# Pi_Tracker2.net
KiCad netlist of a schematic drawn in EAGLE
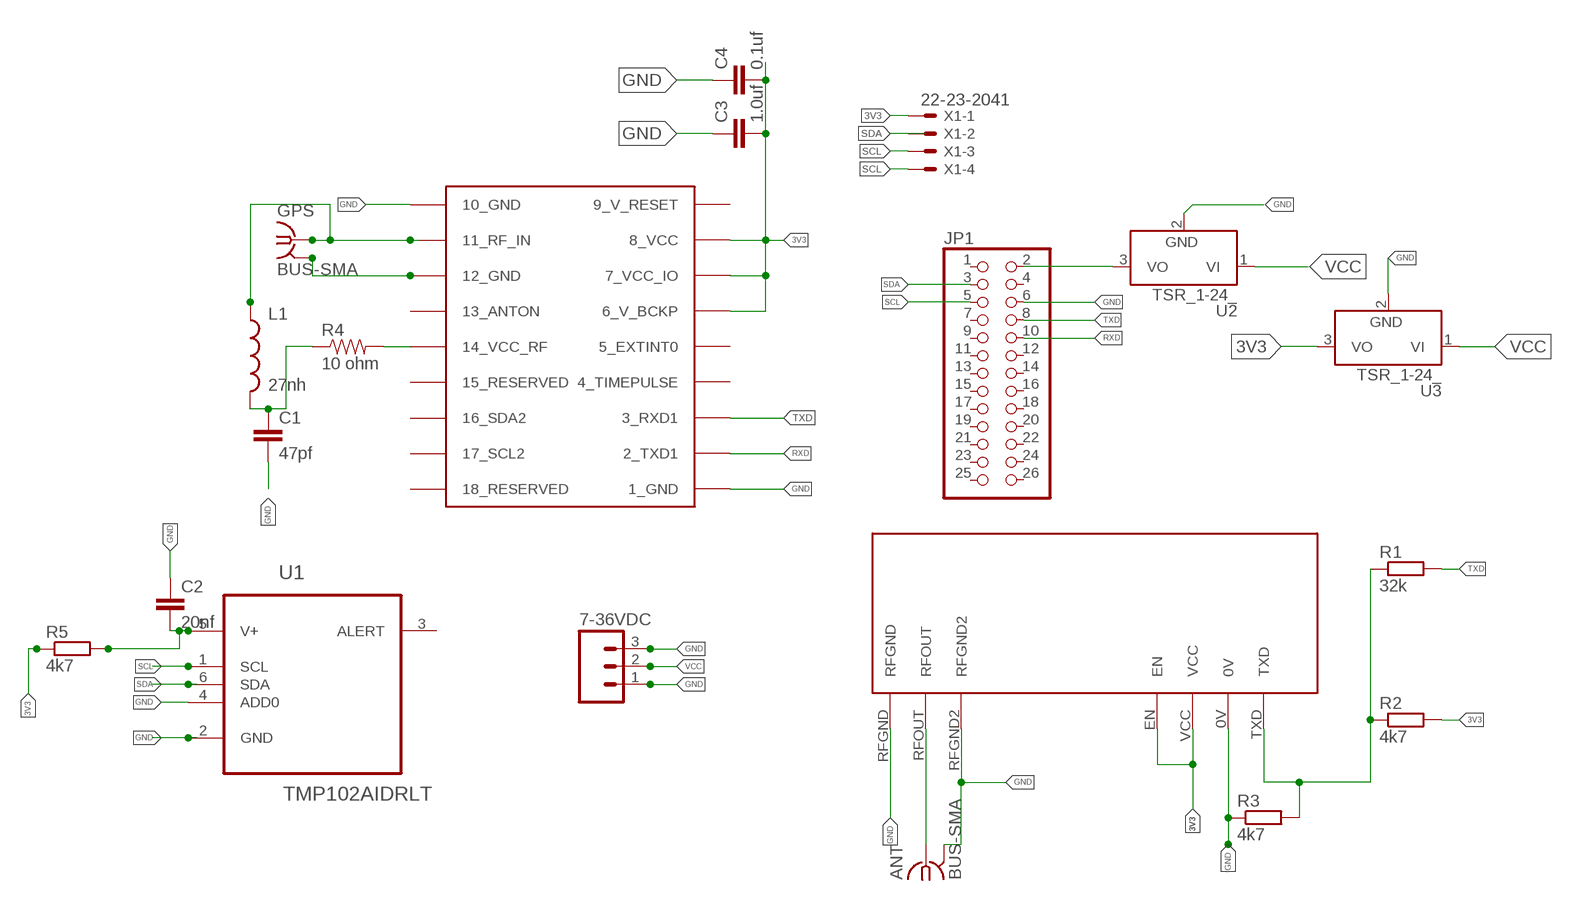
[diagram p0: schematic, sheet 1]

(export (version "E")
  (design (tool "Eeschema 10.0.6"))
  (components
    (comp (ref "7-36VDC")
      (value "M03PTH")
      (footprint "eagle-import:1X03")
      (libsource (lib "eagle-import") (part "M03PTH"))
    )
    (comp (ref "ANT")
      (value "BUS-SMA")
      (footprint "eagle-import:BUS-SMA")
      (libsource (lib "eagle-import") (part "BUS-SMA"))
    )
    (comp (ref "C1")
      (value "47pf")
      (footprint "eagle-import:0603-CAP")
      (libsource (lib "eagle-import") (part "CAP0603-CAP"))
    )
    (comp (ref "C2")
      (value "20nf")
      (footprint "eagle-import:C0603")
      (libsource (lib "eagle-import") (part "C-EUC0603"))
    )
    (comp (ref "C3")
      (value "1.0uf")
      (footprint "eagle-import:C0603")
      (libsource (lib "eagle-import") (part "C-EUC0603"))
    )
    (comp (ref "C4")
      (value "0.1uf")
      (footprint "eagle-import:C0603")
      (libsource (lib "eagle-import") (part "C-EUC0603"))
    )
    (comp (ref "GPS")
      (value "BUS-SMA")
      (footprint "eagle-import:BUS-SMA")
      (libsource (lib "eagle-import") (part "BUS-SMA"))
    )
    (comp (ref "JP1")
      (value "PINHD-2X13")
      (footprint "eagle-import:2X13")
      (libsource (lib "eagle-import") (part "PINHD-2X13"))
    )
    (comp (ref "L1")
      (value "27nh")
      (footprint "eagle-import:0603")
      (libsource (lib "eagle-import") (part "INDUCTOR0603"))
    )
    (comp (ref "R1")
      (value "32k")
      (footprint "eagle-import:R0603")
      (libsource (lib "eagle-import") (part "R-EU_R0603"))
    )
    (comp (ref "R2")
      (value "4k7")
      (footprint "eagle-import:R0603")
      (libsource (lib "eagle-import") (part "R-EU_R0603"))
    )
    (comp (ref "R3")
      (value "4k7")
      (footprint "eagle-import:R0603")
      (libsource (lib "eagle-import") (part "R-EU_R0603"))
    )
    (comp (ref "R4")
      (value "10 ohm")
      (footprint "eagle-import:0603-RES")
      (libsource (lib "eagle-import") (part "RESISTOR0603"))
    )
    (comp (ref "R5")
      (value "4k7")
      (footprint "eagle-import:R0603")
      (libsource (lib "eagle-import") (part "R-EU_R0603"))
    )
    (comp (ref "U$1")
      (value "NTX2")
      (footprint "eagle-import:NTX2")
      (libsource (lib "eagle-import") (part "NTX2"))
    )
    (comp (ref "U$2")
      (value "UBLOX_MAX")
      (footprint "eagle-import:UBLOX_MAX")
      (libsource (lib "eagle-import") (part "UBLOX_MAX"))
    )
    (comp (ref "U1")
      (value "TMP102AIDRLT")
      (footprint "eagle-import:SOT50P160X60-6N")
      (libsource (lib "eagle-import") (part "TMP102AIDRLT"))
    )
    (comp (ref "U2")
      (value "TSR_1-24_")
      (footprint "eagle-import:TSR-1")
      (libsource (lib "eagle-import") (part "TSR_1-24_"))
    )
    (comp (ref "U3")
      (value "TSR_1-24_")
      (footprint "eagle-import:TSR-1")
      (libsource (lib "eagle-import") (part "TSR_1-24_"))
    )
    (comp (ref "X1")
      (value "22-23-2041")
      (footprint "eagle-import:22-23-2041")
      (fields (field (name "MF") "MOLEX"))
      (libsource (lib "eagle-import") (part "22-23-2041"))
    )
  )
  (nets
    (net (code "1") (name "/9_V_RESET") (class "Default")
      (node (ref "U$2") (pin "9_V_RESET") (pinfunction "9_V_RESET_9_V_RESET") (pintype "power_in"))
    )
    (net (code "2") (name "3V3") (class "Default")
      (node (ref "C2") (pin "2") (pinfunction "2_2") (pintype "passive"))
      (node (ref "C3") (pin "2") (pinfunction "2_2") (pintype "passive"))
      (node (ref "C4") (pin "2") (pinfunction "2_2") (pintype "passive"))
      (node (ref "R2") (pin "2") (pinfunction "2_2") (pintype "passive"))
      (node (ref "R5") (pin "1") (pinfunction "1_1") (pintype "passive"))
      (node (ref "R5") (pin "2") (pinfunction "2_2") (pintype "passive"))
      (node (ref "U$1") (pin "EN") (pinfunction "EN_EN") (pintype "bidirectional"))
      (node (ref "U$1") (pin "VCC") (pinfunction "VCC_VCC") (pintype "bidirectional"))
      (node (ref "U$2") (pin "6_V_BCKP") (pinfunction "6_V_BCKP_6_V_BCKP") (pintype "bidirectional"))
      (node (ref "U$2") (pin "7_VCC_IO") (pinfunction "7_VCC_IO_7_VCC_IO") (pintype "power_in"))
      (node (ref "U$2") (pin "8_VCC") (pinfunction "8_VCC_8_VCC") (pintype "power_in"))
      (node (ref "U1") (pin "5") (pinfunction "V+_5") (pintype "power_in"))
      (node (ref "U3") (pin "3") (pinfunction "VO_3") (pintype "power_in"))
      (node (ref "X1") (pin "1") (pinfunction "S_1") (pintype "passive"))
    )
    (net (code "3") (name "GND") (class "Default")
      (node (ref "7-36VDC") (pin "1") (pinfunction "1_1") (pintype "passive"))
      (node (ref "7-36VDC") (pin "3") (pinfunction "3_3") (pintype "passive"))
      (node (ref "ANT") (pin "2") (pinfunction "GND_2") (pintype "power_in"))
      (node (ref "ANT") (pin "3") (pinfunction "GND_3") (pintype "power_in"))
      (node (ref "ANT") (pin "4") (pinfunction "GND_4") (pintype "power_in"))
      (node (ref "ANT") (pin "5") (pinfunction "GND_5") (pintype "power_in"))
      (node (ref "C1") (pin "2") (pinfunction "2_2") (pintype "passive"))
      (node (ref "C2") (pin "1") (pinfunction "1_1") (pintype "passive"))
      (node (ref "C3") (pin "1") (pinfunction "1_1") (pintype "passive"))
      (node (ref "C4") (pin "1") (pinfunction "1_1") (pintype "passive"))
      (node (ref "GPS") (pin "2") (pinfunction "GND_2") (pintype "power_in"))
      (node (ref "GPS") (pin "3") (pinfunction "GND_3") (pintype "power_in"))
      (node (ref "GPS") (pin "4") (pinfunction "GND_4") (pintype "power_in"))
      (node (ref "GPS") (pin "5") (pinfunction "GND_5") (pintype "power_in"))
      (node (ref "JP1") (pin "6") (pinfunction "6_6") (pintype "passive"))
      (node (ref "R3") (pin "1") (pinfunction "1_1") (pintype "passive"))
      (node (ref "U$1") (pin "0V") (pinfunction "0V_0V") (pintype "bidirectional"))
      (node (ref "U$1") (pin "RFGND") (pinfunction "RFGND_RFGND") (pintype "bidirectional"))
      (node (ref "U$1") (pin "RFGND2") (pinfunction "RFGND2_RFGND2") (pintype "bidirectional"))
      (node (ref "U$2") (pin "10_GND") (pinfunction "10_GND_10_GND") (pintype "power_in"))
      (node (ref "U$2") (pin "12_GND") (pinfunction "12_GND_12_GND") (pintype "power_in"))
      (node (ref "U$2") (pin "1_GND") (pinfunction "1_GND_1_GND") (pintype "power_in"))
      (node (ref "U1") (pin "2") (pinfunction "GND_2") (pintype "passive"))
      (node (ref "U1") (pin "4") (pinfunction "ADD0_4") (pintype "input"))
      (node (ref "U2") (pin "2") (pinfunction "GND_2") (pintype "power_in"))
      (node (ref "U3") (pin "2") (pinfunction "GND_2") (pintype "power_in"))
      (node (ref "X1") (pin "4") (pinfunction "S_4") (pintype "passive"))
    )
    (net (code "4") (name "Net-(ANT-Pad1)") (class "Default")
      (node (ref "ANT") (pin "1") (pinfunction "1_1") (pintype "passive"))
      (node (ref "U$1") (pin "RFOUT") (pinfunction "RFOUT_RFOUT") (pintype "bidirectional"))
    )
    (net (code "5") (name "Net-(C1-Pad1)") (class "Default")
      (node (ref "C1") (pin "1") (pinfunction "1_1") (pintype "passive"))
      (node (ref "L1") (pin "2") (pinfunction "2_2") (pintype "passive"))
      (node (ref "R4") (pin "1") (pinfunction "1_1") (pintype "passive"))
    )
    (net (code "6") (name "Net-(GPS-Pad1)") (class "Default")
      (node (ref "GPS") (pin "1") (pinfunction "1_1") (pintype "passive"))
      (node (ref "L1") (pin "1") (pinfunction "1_1") (pintype "passive"))
      (node (ref "U$2") (pin "11_RF_IN") (pinfunction "11_RF_IN_11_RF_IN") (pintype "bidirectional"))
    )
    (net (code "7") (name "Net-(R1-Pad1)") (class "Default")
      (node (ref "R1") (pin "1") (pinfunction "1_1") (pintype "passive"))
      (node (ref "R2") (pin "1") (pinfunction "1_1") (pintype "passive"))
      (node (ref "R3") (pin "2") (pinfunction "2_2") (pintype "passive"))
      (node (ref "U$1") (pin "TXD") (pinfunction "TXD_TXD") (pintype "bidirectional"))
    )
    (net (code "8") (name "Net-(R4-Pad2)") (class "Default")
      (node (ref "R4") (pin "2") (pinfunction "2_2") (pintype "passive"))
      (node (ref "U$2") (pin "14_VCC_RF") (pinfunction "14_VCC_RF_14_VCC_RF") (pintype "bidirectional"))
    )
    (net (code "9") (name "Net-(U2-VO)") (class "Default")
      (node (ref "JP1") (pin "2") (pinfunction "2_2") (pintype "passive"))
      (node (ref "U2") (pin "3") (pinfunction "VO_3") (pintype "power_in"))
    )
    (net (code "10") (name "RXD") (class "Default")
      (node (ref "JP1") (pin "10") (pinfunction "10_10") (pintype "passive"))
      (node (ref "U$2") (pin "2_TXD1") (pinfunction "2_TXD1_2_TXD1") (pintype "bidirectional"))
    )
    (net (code "11") (name "SCL") (class "Default")
      (node (ref "JP1") (pin "5") (pinfunction "5_5") (pintype "passive"))
      (node (ref "U1") (pin "1") (pinfunction "SCL_1") (pintype "bidirectional"))
      (node (ref "X1") (pin "3") (pinfunction "S_3") (pintype "passive"))
    )
    (net (code "12") (name "SDA") (class "Default")
      (node (ref "JP1") (pin "3") (pinfunction "3_3") (pintype "passive"))
      (node (ref "U1") (pin "6") (pinfunction "SDA_6") (pintype "bidirectional"))
      (node (ref "X1") (pin "2") (pinfunction "S_2") (pintype "passive"))
    )
    (net (code "13") (name "TXD") (class "Default")
      (node (ref "JP1") (pin "8") (pinfunction "8_8") (pintype "passive"))
      (node (ref "R1") (pin "2") (pinfunction "2_2") (pintype "passive"))
      (node (ref "U$2") (pin "3_RXD1") (pinfunction "3_RXD1_3_RXD1") (pintype "bidirectional"))
    )
    (net (code "14") (name "VCC") (class "Default")
      (node (ref "7-36VDC") (pin "2") (pinfunction "2_2") (pintype "passive"))
      (node (ref "U2") (pin "1") (pinfunction "VI_1") (pintype "power_in"))
      (node (ref "U3") (pin "1") (pinfunction "VI_1") (pintype "power_in"))
    )
    (net (code "15") (name "unconnected-(JP1-Pad1)") (class "Default")
      (node (ref "JP1") (pin "1") (pinfunction "1_1") (pintype "passive"))
    )
    (net (code "16") (name "unconnected-(JP1-Pad4)") (class "Default")
      (node (ref "JP1") (pin "4") (pinfunction "4_4") (pintype "passive"))
    )
    (net (code "17") (name "unconnected-(JP1-Pad7)") (class "Default")
      (node (ref "JP1") (pin "7") (pinfunction "7_7") (pintype "passive"))
    )
    (net (code "18") (name "unconnected-(JP1-Pad9)") (class "Default")
      (node (ref "JP1") (pin "9") (pinfunction "9_9") (pintype "passive"))
    )
    (net (code "19") (name "unconnected-(JP1-Pad11)") (class "Default")
      (node (ref "JP1") (pin "11") (pinfunction "11_11") (pintype "passive"))
    )
    (net (code "20") (name "unconnected-(JP1-Pad12)") (class "Default")
      (node (ref "JP1") (pin "12") (pinfunction "12_12") (pintype "passive"))
    )
    (net (code "21") (name "unconnected-(JP1-Pad13)") (class "Default")
      (node (ref "JP1") (pin "13") (pinfunction "13_13") (pintype "passive"))
    )
    (net (code "22") (name "unconnected-(JP1-Pad14)") (class "Default")
      (node (ref "JP1") (pin "14") (pinfunction "14_14") (pintype "passive"))
    )
    (net (code "23") (name "unconnected-(JP1-Pad15)") (class "Default")
      (node (ref "JP1") (pin "15") (pinfunction "15_15") (pintype "passive"))
    )
    (net (code "24") (name "unconnected-(JP1-Pad16)") (class "Default")
      (node (ref "JP1") (pin "16") (pinfunction "16_16") (pintype "passive"))
    )
    (net (code "25") (name "unconnected-(JP1-Pad17)") (class "Default")
      (node (ref "JP1") (pin "17") (pinfunction "17_17") (pintype "passive"))
    )
    (net (code "26") (name "unconnected-(JP1-Pad18)") (class "Default")
      (node (ref "JP1") (pin "18") (pinfunction "18_18") (pintype "passive"))
    )
    (net (code "27") (name "unconnected-(JP1-Pad19)") (class "Default")
      (node (ref "JP1") (pin "19") (pinfunction "19_19") (pintype "passive"))
    )
    (net (code "28") (name "unconnected-(JP1-Pad20)") (class "Default")
      (node (ref "JP1") (pin "20") (pinfunction "20_20") (pintype "passive"))
    )
    (net (code "29") (name "unconnected-(JP1-Pad21)") (class "Default")
      (node (ref "JP1") (pin "21") (pinfunction "21_21") (pintype "passive"))
    )
    (net (code "30") (name "unconnected-(JP1-Pad22)") (class "Default")
      (node (ref "JP1") (pin "22") (pinfunction "22_22") (pintype "passive"))
    )
    (net (code "31") (name "unconnected-(JP1-Pad23)") (class "Default")
      (node (ref "JP1") (pin "23") (pinfunction "23_23") (pintype "passive"))
    )
    (net (code "32") (name "unconnected-(JP1-Pad24)") (class "Default")
      (node (ref "JP1") (pin "24") (pinfunction "24_24") (pintype "passive"))
    )
    (net (code "33") (name "unconnected-(JP1-Pad25)") (class "Default")
      (node (ref "JP1") (pin "25") (pinfunction "25_25") (pintype "passive"))
    )
    (net (code "34") (name "unconnected-(JP1-Pad26)") (class "Default")
      (node (ref "JP1") (pin "26") (pinfunction "26_26") (pintype "passive"))
    )
    (net (code "35") (name "unconnected-(U$2-Pad4_TIMEPULSE)") (class "Default")
      (node (ref "U$2") (pin "4_TIMEPULSE") (pinfunction "4_TIMEPULSE_4_TIMEPULSE") (pintype "bidirectional"))
    )
    (net (code "36") (name "unconnected-(U$2-Pad5_EXTINT0)") (class "Default")
      (node (ref "U$2") (pin "5_EXTINT0") (pinfunction "5_EXTINT0_5_EXTINT0") (pintype "bidirectional"))
    )
    (net (code "37") (name "unconnected-(U$2-Pad13_ANTON)") (class "Default")
      (node (ref "U$2") (pin "13_ANTON") (pinfunction "13_ANTON_13_ANTON") (pintype "bidirectional"))
    )
    (net (code "38") (name "unconnected-(U$2-Pad15_RESERVED)") (class "Default")
      (node (ref "U$2") (pin "15_RESERVED") (pinfunction "15_RESERVED_15_RESERVED") (pintype "bidirectional"))
    )
    (net (code "39") (name "unconnected-(U$2-Pad16_SDA2)") (class "Default")
      (node (ref "U$2") (pin "16_SDA2") (pinfunction "16_SDA2_16_SDA2") (pintype "bidirectional"))
    )
    (net (code "40") (name "unconnected-(U$2-Pad17_SCL2)") (class "Default")
      (node (ref "U$2") (pin "17_SCL2") (pinfunction "17_SCL2_17_SCL2") (pintype "bidirectional"))
    )
    (net (code "41") (name "unconnected-(U$2-Pad18_RESERVED)") (class "Default")
      (node (ref "U$2") (pin "18_RESERVED") (pinfunction "18_RESERVED_18_RESERVED") (pintype "bidirectional"))
    )
    (net (code "42") (name "unconnected-(U1-ALERT-Pad3)") (class "Default")
      (node (ref "U1") (pin "3") (pinfunction "ALERT_3") (pintype "output"))
    )
  )
)
